# VCU-S04-V00-PSU5V.net
KiCad netlist of a schematic drawn in Altium Designer
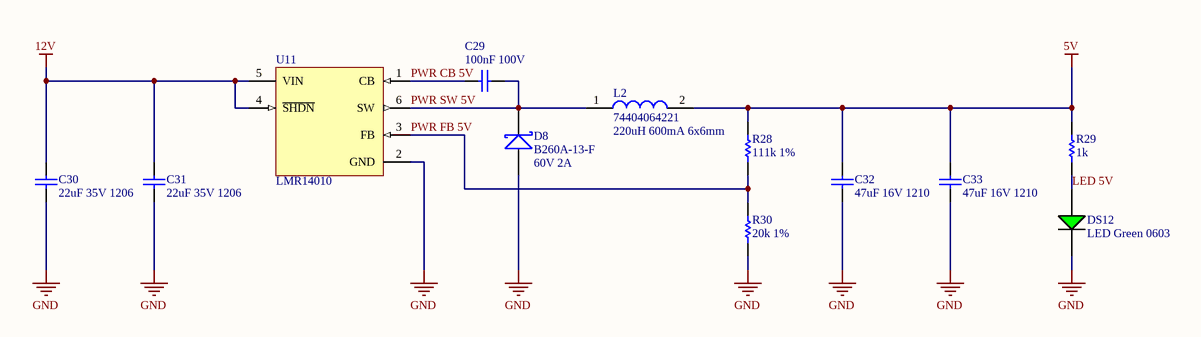
[diagram p0: VCU-S04-V00-PSU5V.SchDoc]

(export (version "E")
  (design (tool "Eeschema 10.0.6"))
  (components
    (comp (ref "C29")
      (value "100nF 100V")
      (footprint "Cap_Ceramic_0603")
      (description "Capacitor, Ceramic, SMD, 100nF, 100V, 5%, X7R, 0603")
      (libsource (lib "StandardCapacitors") (part "100nF 100V 5% X7R 0603"))
    )
    (comp (ref "C30")
      (value "22uF 35V 1206")
      (footprint "Cap_Ceramic_1206")
      (description "Capacitor, Ceramic, SMD, 22uF, 35V, 10%, X7R, 1206")
      (libsource (lib "StandardCapacitors") (part "22uF 35V 10% X7R 1206"))
    )
    (comp (ref "C31")
      (value "22uF 35V 1206")
      (footprint "Cap_Ceramic_1206")
      (description "Capacitor, Ceramic, SMD, 22uF, 35V, 10%, X7R, 1206")
      (libsource (lib "StandardCapacitors") (part "22uF 35V 10% X7R 1206"))
    )
    (comp (ref "C32")
      (value "47uF 16V 1210")
      (footprint "Cap_Ceramic_1210")
      (description "Capacitor, Ceramic, SMD, 47uF, 16V, 5%, X7R, 1210")
      (libsource (lib "StandardCapacitors") (part "47uF 16V 10% X7R 1210"))
    )
    (comp (ref "C33")
      (value "47uF 16V 1210")
      (footprint "Cap_Ceramic_1210")
      (description "Capacitor, Ceramic, SMD, 47uF, 16V, 5%, X7R, 1210")
      (libsource (lib "StandardCapacitors") (part "47uF 16V 10% X7R 1210"))
    )
    (comp (ref "D8")
      (value "B260A-13-F")
      (footprint "SMA")
      (description "Diode, Schottky Barrier Rectifier, 60 V, 2 A, B260A-13-F")
      (libsource (lib "QUTMS_DiodeLibrary") (part "B260A-13-F"))
    )
    (comp (ref "DS12")
      (value "LED Green 0603")
      (footprint "LED GREEN 0603")
      (libsource (lib "QUTMS_LEDLibrary") (part "LED Green 0603"))
    )
    (comp (ref "L2")
      (value "74404064221")
      (footprint "Inductor_6x6mm")
      (description "FIXED IND 220UH 660MA 850 MOHM")
      (libsource (lib "QUTMS_InductorLibrary") (part "74404064221"))
    )
    (comp (ref "R28")
      (value "111k 1%")
      (footprint "Res_ThinFilm_0603")
      (description "Resistor, SMD, 111k, 0.1W, 5%, 0603")
      (libsource (lib "StandardResistors") (part "111k 1% 0603"))
    )
    (comp (ref "R29")
      (value "1k")
      (footprint "Res_ThinFilm_0603")
      (description "Resistor, SMD, 1k, 0.1W, 5%, 0603")
      (libsource (lib "StandardResistors") (part "1k 5% 0603"))
    )
    (comp (ref "R30")
      (value "20k 1%")
      (footprint "Res_ThinFilm_0603")
      (description "Resistor, SMD, 20k, 0.1W, 1%, 0603")
      (libsource (lib "StandardResistors") (part "20k 1% 0603"))
    )
    (comp (ref "U11")
      (value "LMR14010")
      (footprint "LMR14010")
      (libsource (lib "QUTMS_PowerSupplyLibrary") (part "LMR14010"))
    )
  )
  (nets
    (net (code "1") (name "/LED 5V") (class "Default")
      (node (ref "DS12") (pin "1") (pinfunction "A_1") (pintype "passive"))
      (node (ref "R29") (pin "1") (pinfunction "1_1") (pintype "passive"))
    )
    (net (code "2") (name "/PWR CB 5V") (class "Default")
      (node (ref "C29") (pin "1") (pinfunction "1_1") (pintype "passive"))
      (node (ref "U11") (pin "1") (pinfunction "CB_1") (pintype "input"))
    )
    (net (code "3") (name "/PWR FB 5V") (class "Default")
      (node (ref "R28") (pin "1") (pinfunction "1_1") (pintype "passive"))
      (node (ref "R30") (pin "2") (pinfunction "2_2") (pintype "passive"))
      (node (ref "U11") (pin "3") (pinfunction "FB_3") (pintype "input"))
    )
    (net (code "4") (name "/PWR SW 5V") (class "Default")
      (node (ref "C29") (pin "2") (pinfunction "2_2") (pintype "passive"))
      (node (ref "D8") (pin "K") (pinfunction "K_K") (pintype "passive"))
      (node (ref "L2") (pin "1") (pinfunction "1_1") (pintype "passive"))
      (node (ref "U11") (pin "6") (pinfunction "SW_6") (pintype "output"))
    )
    (net (code "5") (name "5V") (class "Default")
      (node (ref "C32") (pin "2") (pinfunction "2_2") (pintype "passive"))
      (node (ref "C33") (pin "2") (pinfunction "2_2") (pintype "passive"))
      (node (ref "L2") (pin "2") (pinfunction "2_2") (pintype "passive"))
      (node (ref "R28") (pin "2") (pinfunction "2_2") (pintype "passive"))
      (node (ref "R29") (pin "2") (pinfunction "2_2") (pintype "passive"))
    )
    (net (code "6") (name "12V") (class "Default")
      (node (ref "C30") (pin "2") (pinfunction "2_2") (pintype "passive"))
      (node (ref "C31") (pin "2") (pinfunction "2_2") (pintype "passive"))
      (node (ref "U11") (pin "4") (pinfunction "~{SHDN}_4") (pintype "input"))
      (node (ref "U11") (pin "5") (pinfunction "VIN_5") (pintype "power_in"))
    )
    (net (code "7") (name "GND") (class "Default")
      (node (ref "C30") (pin "1") (pinfunction "1_1") (pintype "passive"))
      (node (ref "C31") (pin "1") (pinfunction "1_1") (pintype "passive"))
      (node (ref "C32") (pin "1") (pinfunction "1_1") (pintype "passive"))
      (node (ref "C33") (pin "1") (pinfunction "1_1") (pintype "passive"))
      (node (ref "D8") (pin "A") (pinfunction "A_A") (pintype "passive"))
      (node (ref "DS12") (pin "2") (pinfunction "C_2") (pintype "passive"))
      (node (ref "R30") (pin "1") (pinfunction "1_1") (pintype "passive"))
      (node (ref "U11") (pin "2") (pinfunction "GND_2") (pintype "power_in"))
    )
  )
)
